# core.net
KiCad netlist of a schematic drawn in EAGLE
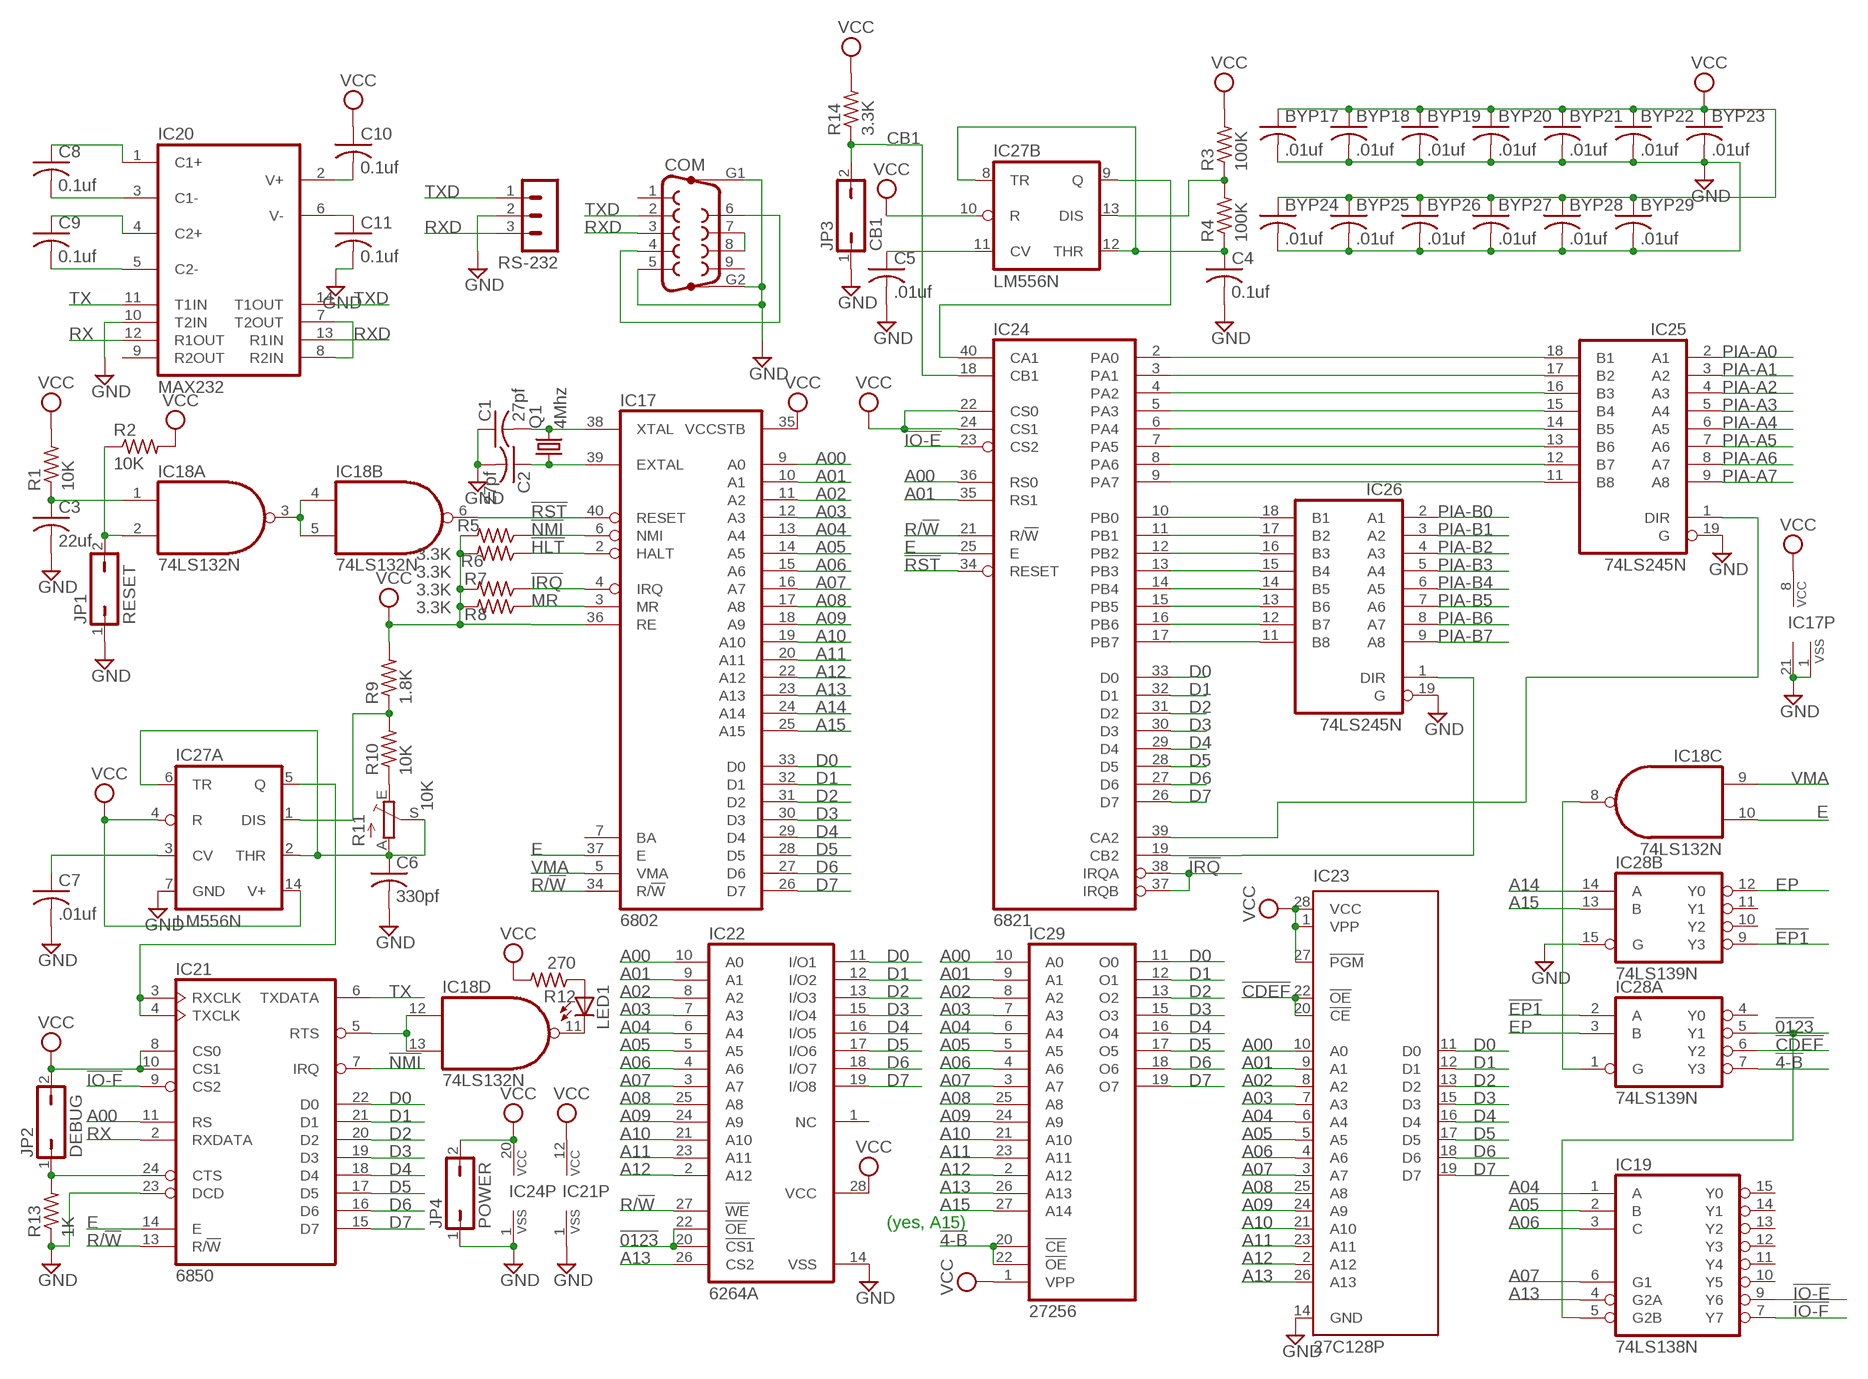
[diagram p0: schematic, sheet 1]
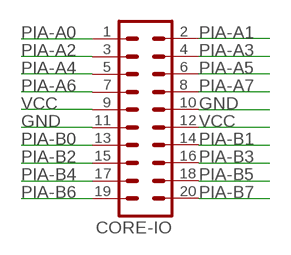
[diagram p1: schematic, sheet 2]

(export (version "E")
  (design (tool "Eeschema 10.0.6"))
  (components
    (comp (ref "CORE-IO")
      (value "MA10-2")
      (footprint "eagle-import:MA10-2")
      (libsource (lib "eagle-import") (part "MA10-2"))
    )
    (comp (ref "BYP17")
      (value ".01uf")
      (footprint "eagle-import:C050-025X075")
      (libsource (lib "eagle-import") (part "C-US050-025X075"))
    )
    (comp (ref "BYP18")
      (value ".01uf")
      (footprint "eagle-import:C050-025X075")
      (libsource (lib "eagle-import") (part "C-US050-025X075"))
    )
    (comp (ref "BYP19")
      (value ".01uf")
      (footprint "eagle-import:C050-025X075")
      (libsource (lib "eagle-import") (part "C-US050-025X075"))
    )
    (comp (ref "BYP20")
      (value ".01uf")
      (footprint "eagle-import:C050-025X075")
      (libsource (lib "eagle-import") (part "C-US050-025X075"))
    )
    (comp (ref "BYP21")
      (value ".01uf")
      (footprint "eagle-import:C050-025X075")
      (libsource (lib "eagle-import") (part "C-US050-025X075"))
    )
    (comp (ref "BYP22")
      (value ".01uf")
      (footprint "eagle-import:C050-025X075")
      (libsource (lib "eagle-import") (part "C-US050-025X075"))
    )
    (comp (ref "BYP23")
      (value ".01uf")
      (footprint "eagle-import:C050-025X075")
      (libsource (lib "eagle-import") (part "C-US050-025X075"))
    )
    (comp (ref "BYP24")
      (value ".01uf")
      (footprint "eagle-import:C050-025X075")
      (libsource (lib "eagle-import") (part "C-US050-025X075"))
    )
    (comp (ref "BYP25")
      (value ".01uf")
      (footprint "eagle-import:C050-025X075")
      (libsource (lib "eagle-import") (part "C-US050-025X075"))
    )
    (comp (ref "BYP26")
      (value ".01uf")
      (footprint "eagle-import:C050-025X075")
      (libsource (lib "eagle-import") (part "C-US050-025X075"))
    )
    (comp (ref "BYP27")
      (value ".01uf")
      (footprint "eagle-import:C050-025X075")
      (libsource (lib "eagle-import") (part "C-US050-025X075"))
    )
    (comp (ref "BYP28")
      (value ".01uf")
      (footprint "eagle-import:C050-025X075")
      (libsource (lib "eagle-import") (part "C-US050-025X075"))
    )
    (comp (ref "BYP29")
      (value ".01uf")
      (footprint "eagle-import:C050-025X075")
      (libsource (lib "eagle-import") (part "C-US050-025X075"))
    )
    (comp (ref "C1")
      (value "27pf")
      (footprint "eagle-import:C050-025X075")
      (libsource (lib "eagle-import") (part "C-US050-025X075"))
    )
    (comp (ref "C2")
      (value "27pf")
      (footprint "eagle-import:C050-025X075")
      (libsource (lib "eagle-import") (part "C-US050-025X075"))
    )
    (comp (ref "C3")
      (value "22uf")
      (footprint "eagle-import:C102-043X133")
      (libsource (lib "eagle-import") (part "C-US102-043X133"))
    )
    (comp (ref "C4")
      (value "0.1uf")
      (footprint "eagle-import:C050-025X075")
      (libsource (lib "eagle-import") (part "C-US050-025X075"))
    )
    (comp (ref "C5")
      (value ".01uf")
      (footprint "eagle-import:C050-025X075")
      (libsource (lib "eagle-import") (part "C-US050-025X075"))
    )
    (comp (ref "C6")
      (value "330pf")
      (footprint "eagle-import:C050-025X075")
      (libsource (lib "eagle-import") (part "C-US050-025X075"))
    )
    (comp (ref "C7")
      (value ".01uf")
      (footprint "eagle-import:C050-025X075")
      (libsource (lib "eagle-import") (part "C-US050-025X075"))
    )
    (comp (ref "C8")
      (value "0.1uf")
      (footprint "eagle-import:C050-025X075")
      (libsource (lib "eagle-import") (part "C-US050-025X075"))
    )
    (comp (ref "C9")
      (value "0.1uf")
      (footprint "eagle-import:C050-025X075")
      (libsource (lib "eagle-import") (part "C-US050-025X075"))
    )
    (comp (ref "C10")
      (value "0.1uf")
      (footprint "eagle-import:C050-025X075")
      (libsource (lib "eagle-import") (part "C-US050-025X075"))
    )
    (comp (ref "C11")
      (value "0.1uf")
      (footprint "eagle-import:C050-025X075")
      (libsource (lib "eagle-import") (part "C-US050-025X075"))
    )
    (comp (ref "COM")
      (value "F09HP")
      (footprint "eagle-import:F09HP")
      (libsource (lib "eagle-import") (part "F09HP"))
    )
    (comp (ref "IC17")
      (value "6802")
      (footprint "eagle-import:DIL40")
      (libsource (lib "eagle-import") (part "6802"))
    )
    (comp (ref "IC18")
      (value "74LS132N")
      (footprint "eagle-import:DIL14")
      (libsource (lib "eagle-import") (part "7400NLS"))
    )
    (comp (ref "IC19")
      (value "74LS138N")
      (footprint "eagle-import:DIL16")
      (libsource (lib "eagle-import") (part "74138NLS"))
    )
    (comp (ref "IC20")
      (value "MAX232")
      (footprint "eagle-import:DIL16")
      (fields (field (name "MF") "MAXIM") (field (name "MPN") "MAX232ACPE+"))
      (libsource (lib "eagle-import") (part "MAX232"))
    )
    (comp (ref "IC21")
      (value "6850")
      (footprint "eagle-import:DIL24")
      (fields (field (name "MF") "NTE ELECTRONICS") (field (name "MPN") "NTE6850"))
      (libsource (lib "eagle-import") (part "6850"))
    )
    (comp (ref "IC22")
      (value "6264A")
      (footprint "eagle-import:DIL28-6")
      (libsource (lib "eagle-import") (part "6264A"))
    )
    (comp (ref "IC23")
      (value "27C128P")
      (footprint "eagle-import:DIL28-6")
      (libsource (lib "eagle-import") (part "27128PC"))
    )
    (comp (ref "IC24")
      (value "6821")
      (footprint "eagle-import:DIL40")
      (fields (field (name "MF") "NTE ELECTRONICS") (field (name "MPN") "NTE6821"))
      (libsource (lib "eagle-import") (part "6821"))
    )
    (comp (ref "IC25")
      (value "74LS245N")
      (footprint "eagle-import:DIL20")
      (libsource (lib "eagle-import") (part "74245NLS"))
    )
    (comp (ref "IC26")
      (value "74LS245N")
      (footprint "eagle-import:DIL20")
      (libsource (lib "eagle-import") (part "74245NLS"))
    )
    (comp (ref "IC27")
      (value "LM556N")
      (footprint "eagle-import:DIL14")
      (libsource (lib "eagle-import") (part "556NLM"))
    )
    (comp (ref "IC28")
      (value "74LS139N")
      (footprint "eagle-import:DIL16")
      (libsource (lib "eagle-import") (part "74139NLS"))
    )
    (comp (ref "IC29")
      (value "27256")
      (footprint "eagle-import:DIL28")
      (libsource (lib "eagle-import") (part "27256"))
    )
    (comp (ref "JP1")
      (value "RESET")
      (footprint "eagle-import:JP1")
      (libsource (lib "eagle-import") (part "JP1Q"))
    )
    (comp (ref "JP2")
      (value "DEBUG")
      (footprint "eagle-import:JP1")
      (libsource (lib "eagle-import") (part "JP1Q"))
    )
    (comp (ref "JP3")
      (value "CB1")
      (footprint "eagle-import:JP1")
      (libsource (lib "eagle-import") (part "JP1Q"))
    )
    (comp (ref "JP4")
      (value "POWER")
      (footprint "eagle-import:JP1")
      (libsource (lib "eagle-import") (part "JP1Q"))
    )
    (comp (ref "LED1")
      (value "LED3MM")
      (footprint "eagle-import:LED3MM")
      (libsource (lib "eagle-import") (part "LED3MM"))
    )
    (comp (ref "Q1")
      (value "4Mhz")
      (footprint "eagle-import:HC18U-V")
      (libsource (lib "eagle-import") (part "CRYSTALHC18U-V"))
    )
    (comp (ref "R1")
      (value "10K")
      (footprint "eagle-import:0207_7")
      (libsource (lib "eagle-import") (part "R-US_0207/7"))
    )
    (comp (ref "R2")
      (value "10K")
      (footprint "eagle-import:0207_7")
      (libsource (lib "eagle-import") (part "R-US_0207/7"))
    )
    (comp (ref "R3")
      (value "100K")
      (footprint "eagle-import:0207_7")
      (libsource (lib "eagle-import") (part "R-US_0207/7"))
    )
    (comp (ref "R4")
      (value "100K")
      (footprint "eagle-import:0207_7")
      (libsource (lib "eagle-import") (part "R-US_0207/7"))
    )
    (comp (ref "R5")
      (value "3.3K")
      (footprint "eagle-import:0207_7")
      (libsource (lib "eagle-import") (part "R-US_0207/7"))
    )
    (comp (ref "R6")
      (value "3.3K")
      (footprint "eagle-import:0207_7")
      (libsource (lib "eagle-import") (part "R-US_0207/7"))
    )
    (comp (ref "R7")
      (value "3.3K")
      (footprint "eagle-import:0207_7")
      (libsource (lib "eagle-import") (part "R-US_0207/7"))
    )
    (comp (ref "R8")
      (value "3.3K")
      (footprint "eagle-import:0207_7")
      (libsource (lib "eagle-import") (part "R-US_0207/7"))
    )
    (comp (ref "R9")
      (value "1.8K")
      (footprint "eagle-import:0207_7")
      (libsource (lib "eagle-import") (part "R-US_0207/7"))
    )
    (comp (ref "R10")
      (value "10K")
      (footprint "eagle-import:0207_7")
      (libsource (lib "eagle-import") (part "R-US_0207/7"))
    )
    (comp (ref "R11")
      (value "10K")
      (footprint "eagle-import:SP19L")
      (libsource (lib "eagle-import") (part "TRIM_EU-B90P"))
    )
    (comp (ref "R12")
      (value "270")
      (footprint "eagle-import:0207_7")
      (libsource (lib "eagle-import") (part "R-US_0207/7"))
    )
    (comp (ref "R13")
      (value "1K")
      (footprint "eagle-import:0207_7")
      (libsource (lib "eagle-import") (part "R-US_0207/7"))
    )
    (comp (ref "R14")
      (value "3.3K")
      (footprint "eagle-import:0207_7")
      (libsource (lib "eagle-import") (part "R-US_0207/7"))
    )
    (comp (ref "RS-232")
      (value "MA03-1")
      (footprint "eagle-import:MA03-1")
      (libsource (lib "eagle-import") (part "MA03-1"))
    )
  )
  (nets
    (net (code "1") (name "A00") (class "Default")
      (node (ref "IC17") (pin "9") (pinfunction "A0_9") (pintype "output"))
      (node (ref "IC21") (pin "11") (pinfunction "RS_11") (pintype "input"))
      (node (ref "IC22") (pin "10") (pinfunction "A0_10") (pintype "input"))
      (node (ref "IC23") (pin "10") (pinfunction "A0_10") (pintype "input"))
      (node (ref "IC24") (pin "36") (pinfunction "RS0_36") (pintype "input"))
      (node (ref "IC29") (pin "10") (pinfunction "A0_10") (pintype "input"))
    )
    (net (code "2") (name "A01") (class "Default")
      (node (ref "IC17") (pin "10") (pinfunction "A1_10") (pintype "output"))
      (node (ref "IC22") (pin "9") (pinfunction "A1_9") (pintype "input"))
      (node (ref "IC23") (pin "9") (pinfunction "A1_9") (pintype "input"))
      (node (ref "IC24") (pin "35") (pinfunction "RS1_35") (pintype "input"))
      (node (ref "IC29") (pin "9") (pinfunction "A1_9") (pintype "input"))
    )
    (net (code "3") (name "A02") (class "Default")
      (node (ref "IC17") (pin "11") (pinfunction "A2_11") (pintype "output"))
      (node (ref "IC22") (pin "8") (pinfunction "A2_8") (pintype "input"))
      (node (ref "IC23") (pin "8") (pinfunction "A2_8") (pintype "input"))
      (node (ref "IC29") (pin "8") (pinfunction "A2_8") (pintype "input"))
    )
    (net (code "4") (name "A03") (class "Default")
      (node (ref "IC17") (pin "12") (pinfunction "A3_12") (pintype "output"))
      (node (ref "IC22") (pin "7") (pinfunction "A3_7") (pintype "input"))
      (node (ref "IC23") (pin "7") (pinfunction "A3_7") (pintype "input"))
      (node (ref "IC29") (pin "7") (pinfunction "A3_7") (pintype "input"))
    )
    (net (code "5") (name "A04") (class "Default")
      (node (ref "IC17") (pin "13") (pinfunction "A4_13") (pintype "output"))
      (node (ref "IC19") (pin "1") (pinfunction "A_1") (pintype "input"))
      (node (ref "IC22") (pin "6") (pinfunction "A4_6") (pintype "input"))
      (node (ref "IC23") (pin "6") (pinfunction "A4_6") (pintype "input"))
      (node (ref "IC29") (pin "6") (pinfunction "A4_6") (pintype "input"))
    )
    (net (code "6") (name "A05") (class "Default")
      (node (ref "IC17") (pin "14") (pinfunction "A5_14") (pintype "output"))
      (node (ref "IC19") (pin "2") (pinfunction "B_2") (pintype "input"))
      (node (ref "IC22") (pin "5") (pinfunction "A5_5") (pintype "input"))
      (node (ref "IC23") (pin "5") (pinfunction "A5_5") (pintype "input"))
      (node (ref "IC29") (pin "5") (pinfunction "A5_5") (pintype "input"))
    )
    (net (code "7") (name "A06") (class "Default")
      (node (ref "IC17") (pin "15") (pinfunction "A6_15") (pintype "output"))
      (node (ref "IC19") (pin "3") (pinfunction "C_3") (pintype "input"))
      (node (ref "IC22") (pin "4") (pinfunction "A6_4") (pintype "input"))
      (node (ref "IC23") (pin "4") (pinfunction "A6_4") (pintype "input"))
      (node (ref "IC29") (pin "4") (pinfunction "A6_4") (pintype "input"))
    )
    (net (code "8") (name "A07") (class "Default")
      (node (ref "IC17") (pin "16") (pinfunction "A7_16") (pintype "output"))
      (node (ref "IC19") (pin "6") (pinfunction "G1_6") (pintype "input"))
      (node (ref "IC22") (pin "3") (pinfunction "A7_3") (pintype "input"))
      (node (ref "IC23") (pin "3") (pinfunction "A7_3") (pintype "input"))
      (node (ref "IC29") (pin "3") (pinfunction "A7_3") (pintype "input"))
    )
    (net (code "9") (name "A08") (class "Default")
      (node (ref "IC17") (pin "17") (pinfunction "A8_17") (pintype "output"))
      (node (ref "IC22") (pin "25") (pinfunction "A8_25") (pintype "input"))
      (node (ref "IC23") (pin "25") (pinfunction "A8_25") (pintype "input"))
      (node (ref "IC29") (pin "25") (pinfunction "A8_25") (pintype "input"))
    )
    (net (code "10") (name "A09") (class "Default")
      (node (ref "IC17") (pin "18") (pinfunction "A9_18") (pintype "output"))
      (node (ref "IC22") (pin "24") (pinfunction "A9_24") (pintype "input"))
      (node (ref "IC23") (pin "24") (pinfunction "A9_24") (pintype "input"))
      (node (ref "IC29") (pin "24") (pinfunction "A9_24") (pintype "input"))
    )
    (net (code "11") (name "A10") (class "Default")
      (node (ref "IC17") (pin "19") (pinfunction "A10_19") (pintype "output"))
      (node (ref "IC22") (pin "21") (pinfunction "A10_21") (pintype "input"))
      (node (ref "IC23") (pin "21") (pinfunction "A10_21") (pintype "input"))
      (node (ref "IC29") (pin "21") (pinfunction "A10_21") (pintype "input"))
    )
    (net (code "12") (name "A11") (class "Default")
      (node (ref "IC17") (pin "20") (pinfunction "A11_20") (pintype "output"))
      (node (ref "IC22") (pin "23") (pinfunction "A11_23") (pintype "input"))
      (node (ref "IC23") (pin "23") (pinfunction "A11_23") (pintype "input"))
      (node (ref "IC29") (pin "23") (pinfunction "A11_23") (pintype "input"))
    )
    (net (code "13") (name "A12") (class "Default")
      (node (ref "IC17") (pin "22") (pinfunction "A12_22") (pintype "output"))
      (node (ref "IC22") (pin "2") (pinfunction "A12_2") (pintype "input"))
      (node (ref "IC23") (pin "2") (pinfunction "A12_2") (pintype "input"))
      (node (ref "IC29") (pin "2") (pinfunction "A12_2") (pintype "input"))
    )
    (net (code "14") (name "A13") (class "Default")
      (node (ref "IC17") (pin "23") (pinfunction "A13_23") (pintype "output"))
      (node (ref "IC19") (pin "4") (pinfunction "G2A_4") (pintype "input"))
      (node (ref "IC22") (pin "26") (pinfunction "CS2_26") (pintype "input"))
      (node (ref "IC23") (pin "26") (pinfunction "A13_26") (pintype "input"))
      (node (ref "IC29") (pin "26") (pinfunction "A13_26") (pintype "input"))
    )
    (net (code "15") (name "A14") (class "Default")
      (node (ref "IC17") (pin "24") (pinfunction "A14_24") (pintype "output"))
      (node (ref "IC28") (pin "14") (pinfunction "A_14") (pintype "input"))
    )
    (net (code "16") (name "A15") (class "Default")
      (node (ref "IC17") (pin "25") (pinfunction "A15_25") (pintype "output"))
      (node (ref "IC28") (pin "13") (pinfunction "B_13") (pintype "input"))
      (node (ref "IC29") (pin "27") (pinfunction "A14_27") (pintype "input"))
    )
    (net (code "17") (name "CB1") (class "Default")
      (node (ref "IC24") (pin "18") (pinfunction "CB1_18") (pintype "input"))
      (node (ref "JP3") (pin "2") (pinfunction "2_2") (pintype "passive"))
      (node (ref "R14") (pin "1") (pinfunction "1_1") (pintype "passive"))
    )
    (net (code "18") (name "D0") (class "Default")
      (node (ref "IC17") (pin "33") (pinfunction "D0_33") (pintype "bidirectional"))
      (node (ref "IC21") (pin "22") (pinfunction "D0_22") (pintype "bidirectional"))
      (node (ref "IC22") (pin "11") (pinfunction "I/O1_11") (pintype "bidirectional"))
      (node (ref "IC23") (pin "11") (pinfunction "D0_11") (pintype "tri_state"))
      (node (ref "IC24") (pin "33") (pinfunction "D0_33") (pintype "bidirectional"))
      (node (ref "IC29") (pin "11") (pinfunction "O0_11") (pintype "tri_state"))
    )
    (net (code "19") (name "D1") (class "Default")
      (node (ref "IC17") (pin "32") (pinfunction "D1_32") (pintype "bidirectional"))
      (node (ref "IC21") (pin "21") (pinfunction "D1_21") (pintype "bidirectional"))
      (node (ref "IC22") (pin "12") (pinfunction "I/O2_12") (pintype "bidirectional"))
      (node (ref "IC23") (pin "12") (pinfunction "D1_12") (pintype "tri_state"))
      (node (ref "IC24") (pin "32") (pinfunction "D1_32") (pintype "bidirectional"))
      (node (ref "IC29") (pin "12") (pinfunction "O1_12") (pintype "tri_state"))
    )
    (net (code "20") (name "D2") (class "Default")
      (node (ref "IC17") (pin "31") (pinfunction "D2_31") (pintype "bidirectional"))
      (node (ref "IC21") (pin "20") (pinfunction "D2_20") (pintype "bidirectional"))
      (node (ref "IC22") (pin "13") (pinfunction "I/O3_13") (pintype "bidirectional"))
      (node (ref "IC23") (pin "13") (pinfunction "D2_13") (pintype "tri_state"))
      (node (ref "IC24") (pin "31") (pinfunction "D2_31") (pintype "bidirectional"))
      (node (ref "IC29") (pin "13") (pinfunction "O2_13") (pintype "tri_state"))
    )
    (net (code "21") (name "D3") (class "Default")
      (node (ref "IC17") (pin "30") (pinfunction "D3_30") (pintype "bidirectional"))
      (node (ref "IC21") (pin "19") (pinfunction "D3_19") (pintype "bidirectional"))
      (node (ref "IC22") (pin "15") (pinfunction "I/O4_15") (pintype "bidirectional"))
      (node (ref "IC23") (pin "15") (pinfunction "D3_15") (pintype "tri_state"))
      (node (ref "IC24") (pin "30") (pinfunction "D3_30") (pintype "bidirectional"))
      (node (ref "IC29") (pin "15") (pinfunction "O3_15") (pintype "tri_state"))
    )
    (net (code "22") (name "D4") (class "Default")
      (node (ref "IC17") (pin "29") (pinfunction "D4_29") (pintype "bidirectional"))
      (node (ref "IC21") (pin "18") (pinfunction "D4_18") (pintype "bidirectional"))
      (node (ref "IC22") (pin "16") (pinfunction "I/O5_16") (pintype "bidirectional"))
      (node (ref "IC23") (pin "16") (pinfunction "D4_16") (pintype "tri_state"))
      (node (ref "IC24") (pin "29") (pinfunction "D4_29") (pintype "bidirectional"))
      (node (ref "IC29") (pin "16") (pinfunction "O4_16") (pintype "tri_state"))
    )
    (net (code "23") (name "D5") (class "Default")
      (node (ref "IC17") (pin "28") (pinfunction "D5_28") (pintype "bidirectional"))
      (node (ref "IC21") (pin "17") (pinfunction "D5_17") (pintype "bidirectional"))
      (node (ref "IC22") (pin "17") (pinfunction "I/O6_17") (pintype "bidirectional"))
      (node (ref "IC23") (pin "17") (pinfunction "D5_17") (pintype "tri_state"))
      (node (ref "IC24") (pin "28") (pinfunction "D5_28") (pintype "bidirectional"))
      (node (ref "IC29") (pin "17") (pinfunction "O5_17") (pintype "tri_state"))
    )
    (net (code "24") (name "D6") (class "Default")
      (node (ref "IC17") (pin "27") (pinfunction "D6_27") (pintype "bidirectional"))
      (node (ref "IC21") (pin "16") (pinfunction "D6_16") (pintype "bidirectional"))
      (node (ref "IC22") (pin "18") (pinfunction "I/O7_18") (pintype "bidirectional"))
      (node (ref "IC23") (pin "18") (pinfunction "D6_18") (pintype "tri_state"))
      (node (ref "IC24") (pin "27") (pinfunction "D6_27") (pintype "bidirectional"))
      (node (ref "IC29") (pin "18") (pinfunction "O6_18") (pintype "tri_state"))
    )
    (net (code "25") (name "D7") (class "Default")
      (node (ref "IC17") (pin "26") (pinfunction "D7_26") (pintype "bidirectional"))
      (node (ref "IC21") (pin "15") (pinfunction "D7_15") (pintype "bidirectional"))
      (node (ref "IC22") (pin "19") (pinfunction "I/O8_19") (pintype "bidirectional"))
      (node (ref "IC23") (pin "19") (pinfunction "D7_19") (pintype "tri_state"))
      (node (ref "IC24") (pin "26") (pinfunction "D7_26") (pintype "bidirectional"))
      (node (ref "IC29") (pin "19") (pinfunction "O7_19") (pintype "tri_state"))
    )
    (net (code "26") (name "E") (class "Default")
      (node (ref "IC17") (pin "37") (pinfunction "E_37") (pintype "output"))
      (node (ref "IC18") (pin "10") (pinfunction "I1_10") (pintype "input"))
      (node (ref "IC21") (pin "14") (pinfunction "E_14") (pintype "input"))
      (node (ref "IC24") (pin "25") (pinfunction "E_25") (pintype "input"))
    )
    (net (code "27") (name "EP") (class "Default")
      (node (ref "IC28") (pin "12") (pinfunction "Y0_12") (pintype "output"))
      (node (ref "IC28") (pin "3") (pinfunction "B_3") (pintype "input"))
    )
    (net (code "28") (name "GND") (class "Default")
      (node (ref "BYP17") (pin "2") (pinfunction "2_2") (pintype "passive"))
      (node (ref "BYP18") (pin "2") (pinfunction "2_2") (pintype "passive"))
      (node (ref "BYP19") (pin "2") (pinfunction "2_2") (pintype "passive"))
      (node (ref "BYP20") (pin "2") (pinfunction "2_2") (pintype "passive"))
      (node (ref "BYP21") (pin "2") (pinfunction "2_2") (pintype "passive"))
      (node (ref "BYP22") (pin "2") (pinfunction "2_2") (pintype "passive"))
      (node (ref "BYP23") (pin "2") (pinfunction "2_2") (pintype "passive"))
      (node (ref "BYP24") (pin "2") (pinfunction "2_2") (pintype "passive"))
      (node (ref "BYP25") (pin "2") (pinfunction "2_2") (pintype "passive"))
      (node (ref "BYP26") (pin "2") (pinfunction "2_2") (pintype "passive"))
      (node (ref "BYP27") (pin "2") (pinfunction "2_2") (pintype "passive"))
      (node (ref "BYP28") (pin "2") (pinfunction "2_2") (pintype "passive"))
      (node (ref "BYP29") (pin "2") (pinfunction "2_2") (pintype "passive"))
      (node (ref "C1") (pin "1") (pinfunction "1_1") (pintype "passive"))
      (node (ref "C11") (pin "2") (pinfunction "2_2") (pintype "passive"))
      (node (ref "C2") (pin "2") (pinfunction "2_2") (pintype "passive"))
      (node (ref "C3") (pin "2") (pinfunction "2_2") (pintype "passive"))
      (node (ref "C4") (pin "2") (pinfunction "2_2") (pintype "passive"))
      (node (ref "C5") (pin "2") (pinfunction "2_2") (pintype "passive"))
      (node (ref "C6") (pin "2") (pinfunction "2_2") (pintype "passive"))
      (node (ref "C7") (pin "2") (pinfunction "2_2") (pintype "passive"))
      (node (ref "COM") (pin "5") (pinfunction "5_5") (pintype "passive"))
      (node (ref "COM") (pin "G1") (pinfunction "G1_G1") (pintype "passive"))
      (node (ref "COM") (pin "G2") (pinfunction "G2_G2") (pintype "passive"))
      (node (ref "CORE-IO") (pin "10") (pinfunction "10_10") (pintype "passive"))
      (node (ref "CORE-IO") (pin "11") (pinfunction "11_11") (pintype "passive"))
      (node (ref "IC17") (pin "1") (pinfunction "VSS_1") (pintype "power_in"))
      (node (ref "IC17") (pin "21") (pinfunction "VSS_21") (pintype "power_in"))
      (node (ref "IC20") (pin "10") (pinfunction "T2IN_10") (pintype "input"))
      (node (ref "IC21") (pin "1") (pinfunction "VSS_1") (pintype "power_in"))
      (node (ref "IC21") (pin "23") (pinfunction "DCD_23") (pintype "input"))
      (node (ref "IC22") (pin "14") (pinfunction "VSS_14") (pintype "power_in"))
      (node (ref "IC23") (pin "14") (pinfunction "GND_14") (pintype "power_in"))
      (node (ref "IC24") (pin "1") (pinfunction "VSS_1") (pintype "power_in"))
      (node (ref "IC25") (pin "19") (pinfunction "G_19") (pintype "input"))
      (node (ref "IC26") (pin "19") (pinfunction "G_19") (pintype "input"))
      (node (ref "IC27") (pin "7") (pinfunction "GND_7") (pintype "power_in"))
      (node (ref "IC28") (pin "15") (pinfunction "G_15") (pintype "input"))
      (node (ref "JP1") (pin "1") (pinfunction "1_1") (pintype "passive"))
      (node (ref "JP3") (pin "1") (pinfunction "1_1") (pintype "passive"))
      (node (ref "JP4") (pin "1") (pinfunction "1_1") (pintype "passive"))
      (node (ref "R13") (pin "1") (pinfunction "1_1") (pintype "passive"))
      (node (ref "RS-232") (pin "2") (pinfunction "2_2") (pintype "passive"))
    )
    (net (code "29") (name "MR") (class "Default")
      (node (ref "IC17") (pin "3") (pinfunction "MR_3") (pintype "input"))
      (node (ref "R8") (pin "1") (pinfunction "1_1") (pintype "passive"))
    )
    (net (code "30") (name "Net-(COM-Pad4)") (class "Default")
      (node (ref "COM") (pin "4") (pinfunction "4_4") (pintype "passive"))
      (node (ref "COM") (pin "6") (pinfunction "6_6") (pintype "passive"))
    )
    (net (code "31") (name "Net-(COM-Pad7)") (class "Default")
      (node (ref "COM") (pin "7") (pinfunction "7_7") (pintype "passive"))
      (node (ref "COM") (pin "8") (pinfunction "8_8") (pintype "passive"))
    )
    (net (code "32") (name "Net-(IC17A-EXTAL)") (class "Default")
      (node (ref "C2") (pin "1") (pinfunction "1_1") (pintype "passive"))
      (node (ref "IC17") (pin "39") (pinfunction "EXTAL_39") (pintype "input"))
      (node (ref "Q1") (pin "1") (pinfunction "1_1") (pintype "passive"))
    )
    (net (code "33") (name "Net-(IC17A-XTAL)") (class "Default")
      (node (ref "C1") (pin "2") (pinfunction "2_2") (pintype "passive"))
      (node (ref "IC17") (pin "38") (pinfunction "XTAL_38") (pintype "input"))
      (node (ref "Q1") (pin "2") (pinfunction "2_2") (pintype "passive"))
    )
    (net (code "34") (name "Net-(IC18A-I0)") (class "Default")
      (node (ref "C3") (pin "1") (pinfunction "1_1") (pintype "passive"))
      (node (ref "IC18") (pin "1") (pinfunction "I0_1") (pintype "input"))
      (node (ref "R1") (pin "1") (pinfunction "1_1") (pintype "passive"))
    )
    (net (code "35") (name "Net-(IC18A-I1)") (class "Default")
      (node (ref "IC18") (pin "2") (pinfunction "I1_2") (pintype "input"))
      (node (ref "JP1") (pin "2") (pinfunction "2_2") (pintype "passive"))
      (node (ref "R2") (pin "1") (pinfunction "1_1") (pintype "passive"))
    )
    (net (code "36") (name "Net-(IC18A-O)") (class "Default")
      (node (ref "IC18") (pin "3") (pinfunction "O_3") (pintype "output"))
      (node (ref "IC18") (pin "4") (pinfunction "I0_4") (pintype "input"))
      (node (ref "IC18") (pin "5") (pinfunction "I1_5") (pintype "input"))
    )
    (net (code "37") (name "Net-(IC18C-O)") (class "Default")
      (node (ref "IC18") (pin "8") (pinfunction "O_8") (pintype "output"))
      (node (ref "IC28") (pin "1") (pinfunction "G_1") (pintype "input"))
    )
    (net (code "38") (name "Net-(IC18D-I0)") (class "Default")
      (node (ref "IC18") (pin "12") (pinfunction "I0_12") (pintype "input"))
      (node (ref "IC18") (pin "13") (pinfunction "I1_13") (pintype "input"))
      (node (ref "IC21") (pin "5") (pinfunction "RTS_5") (pintype "output"))
    )
    (net (code "39") (name "Net-(IC18D-O)") (class "Default")
      (node (ref "IC18") (pin "11") (pinfunction "O_11") (pintype "output"))
      (node (ref "LED1") (pin "K") (pinfunction "C_K") (pintype "passive"))
    )
    (net (code "40") (name "Net-(IC20A-C1+)") (class "Default")
      (node (ref "C8") (pin "1") (pinfunction "1_1") (pintype "passive"))
      (node (ref "IC20") (pin "1") (pinfunction "C1+_1") (pintype "bidirectional"))
    )
    (net (code "41") (name "Net-(IC20A-C1-)") (class "Default")
      (node (ref "C8") (pin "2") (pinfunction "2_2") (pintype "passive"))
      (node (ref "IC20") (pin "3") (pinfunction "C1-_3") (pintype "bidirectional"))
    )
    (net (code "42") (name "Net-(IC20A-C2+)") (class "Default")
      (node (ref "C9") (pin "1") (pinfunction "1_1") (pintype "passive"))
      (node (ref "IC20") (pin "4") (pinfunction "C2+_4") (pintype "bidirectional"))
    )
    (net (code "43") (name "Net-(IC20A-C2-)") (class "Default")
      (node (ref "C9") (pin "2") (pinfunction "2_2") (pintype "passive"))
      (node (ref "IC20") (pin "5") (pinfunction "C2-_5") (pintype "bidirectional"))
    )
    (net (code "44") (name "Net-(IC20A-R2IN)") (class "Default")
      (node (ref "IC20") (pin "7") (pinfunction "T2OUT_7") (pintype "output"))
      (node (ref "IC20") (pin "8") (pinfunction "R2IN_8") (pintype "input"))
    )
    (net (code "45") (name "Net-(IC20A-V+)") (class "Default")
      (node (ref "C10") (pin "2") (pinfunction "2_2") (pintype "passive"))
      (node (ref "IC20") (pin "2") (pinfunction "V+_2") (pintype "bidirectional"))
    )
    (net (code "46") (name "Net-(IC20A-V-)") (class "Default")
      (node (ref "C11") (pin "1") (pinfunction "1_1") (pintype "passive"))
      (node (ref "IC20") (pin "6") (pinfunction "V-_6") (pintype "bidirectional"))
    )
    (net (code "47") (name "Net-(IC21A-CTS)") (class "Default")
      (node (ref "IC21") (pin "24") (pinfunction "CTS_24") (pintype "input"))
      (node (ref "JP2") (pin "1") (pinfunction "1_1") (pintype "passive"))
      (node (ref "R13") (pin "2") (pinfunction "2_2") (pintype "passive"))
    )
    (net (code "48") (name "Net-(IC21A-RXCLK)") (class "Default")
      (node (ref "IC21") (pin "3") (pinfunction "RXCLK_3") (pintype "input"))
      (node (ref "IC21") (pin "4") (pinfunction "TXCLK_4") (pintype "input"))
      (node (ref "IC27") (pin "5") (pinfunction "Q_5") (pintype "output"))
    )
    (net (code "49") (name "Net-(IC24A-CA1)") (class "Default")
      (node (ref "IC24") (pin "40") (pinfunction "CA1_40") (pintype "input"))
      (node (ref "IC27") (pin "9") (pinfunction "Q_9") (pintype "output"))
    )
    (net (code "50") (name "Net-(IC24A-CA2)") (class "Default")
      (node (ref "IC24") (pin "39") (pinfunction "CA2_39") (pintype "bidirectional"))
      (node (ref "IC25") (pin "1") (pinfunction "DIR_1") (pintype "input"))
    )
    (net (code "51") (name "Net-(IC24A-CB2)") (class "Default")
      (node (ref "IC24") (pin "19") (pinfunction "CB2_19") (pintype "bidirectional"))
      (node (ref "IC26") (pin "1") (pinfunction "DIR_1") (pintype "input"))
    )
    (net (code "52") (name "Net-(IC24A-PA0)") (class "Default")
      (node (ref "IC24") (pin "2") (pinfunction "PA0_2") (pintype "bidirectional"))
      (node (ref "IC25") (pin "18") (pinfunction "B1_18") (pintype "bidirectional"))
    )
    (net (code "53") (name "Net-(IC24A-PA1)") (class "Default")
      (node (ref "IC24") (pin "3") (pinfunction "PA1_3") (pintype "bidirectional"))
      (node (ref "IC25") (pin "17") (pinfunction "B2_17") (pintype "bidirectional"))
    )
    (net (code "54") (name "Net-(IC24A-PA2)") (class "Default")
      (node (ref "IC24") (pin "4") (pinfunction "PA2_4") (pintype "bidirectional"))
      (node (ref "IC25") (pin "16") (pinfunction "B3_16") (pintype "bidirectional"))
    )
    (net (code "55") (name "Net-(IC24A-PA3)") (class "Default")
      (node (ref "IC24") (pin "5") (pinfunction "PA3_5") (pintype "bidirectional"))
      (node (ref "IC25") (pin "15") (pinfunction "B4_15") (pintype "bidirectional"))
    )
    (net (code "56") (name "Net-(IC24A-PA4)") (class "Default")
      (node (ref "IC24") (pin "6") (pinfunction "PA4_6") (pintype "bidirectional"))
      (node (ref "IC25") (pin "14") (pinfunction "B5_14") (pintype "bidirectional"))
    )
    (net (code "57") (name "Net-(IC24A-PA5)") (class "Default")
      (node (ref "IC24") (pin "7") (pinfunction "PA5_7") (pintype "bidirectional"))
      (node (ref "IC25") (pin "13") (pinfunction "B6_13") (pintype "bidirectional"))
    )
    (net (code "58") (name "Net-(IC24A-PA6)") (class "Default")
      (node (ref "IC24") (pin "8") (pinfunction "PA6_8") (pintype "bidirectional"))
      (node (ref "IC25") (pin "12") (pinfunction "B7_12") (pintype "bidirectional"))
    )
    (net (code "59") (name "Net-(IC24A-PA7)") (class "Default")
      (node (ref "IC24") (pin "9") (pinfunction "PA7_9") (pintype "bidirectional"))
      (node (ref "IC25") (pin "11") (pinfunction "B8_11") (pintype "bidirectional"))
    )
    (net (code "60") (name "Net-(IC24A-PB0)") (class "Default")
      (node (ref "IC24") (pin "10") (pinfunction "PB0_10") (pintype "bidirectional"))
      (node (ref "IC26") (pin "18") (pinfunction "B1_18") (pintype "bidirectional"))
    )
    (net (code "61") (name "Net-(IC24A-PB1)") (class "Default")
      (node (ref "IC24") (pin "11") (pinfunction "PB1_11") (pintype "bidirectional"))
      (node (ref "IC26") (pin "17") (pinfunction "B2_17") (pintype "bidirectional"))
    )
    (net (code "62") (name "Net-(IC24A-PB2)") (class "Default")
      (node (ref "IC24") (pin "12") (pinfunction "PB2_12") (pintype "bidirectional"))
      (node (ref "IC26") (pin "16") (pinfunction "B3_16") (pintype "bidirectional"))
    )
    (net (code "63") (name "Net-(IC24A-PB3)") (class "Default")
      (node (ref "IC24") (pin "13") (pinfunction "PB3_13") (pintype "bidirectional"))
      (node (ref "IC26") (pin "15") (pinfunction "B4_15") (pintype "bidirectional"))
    )
    (net (code "64") (name "Net-(IC24A-PB4)") (class "Default")
      (node (ref "IC24") (pin "14") (pinfunction "PB4_14") (pintype "bidirectional"))
      (node (ref "IC26") (pin "14") (pinfunction "B5_14") (pintype "bidirectional"))
    )
    (net (code "65") (name "Net-(IC24A-PB5)") (class "Default")
      (node (ref "IC24") (pin "15") (pinfunction "PB5_15") (pintype "bidirectional"))
      (node (ref "IC26") (pin "13") (pinfunction "B6_13") (pintype "bidirectional"))
    )
    (net (code "66") (name "Net-(IC24A-PB6)") (class "Default")
      (node (ref "IC24") (pin "16") (pinfunction "PB6_16") (pintype "bidirectional"))
      (node (ref "IC26") (pin "12") (pinfunction "B7_12") (pintype "bidirectional"))
    )
    (net (code "67") (name "Net-(IC24A-PB7)") (class "Default")
      (node (ref "IC24") (pin "17") (pinfunction "PB7_17") (pintype "bidirectional"))
      (node (ref "IC26") (pin "11") (pinfunction "B8_11") (pintype "bidirectional"))
    )
    (net (code "68") (name "Net-(IC27A-CV)") (class "Default")
      (node (ref "C7") (pin "1") (pinfunction "1_1") (pintype "passive"))
      (node (ref "IC27") (pin "3") (pinfunction "CV_3") (pintype "input"))
    )
    (net (code "69") (name "Net-(IC27A-DIS)") (class "Default")
      (node (ref "IC27") (pin "1") (pinfunction "DIS_1") (pintype "input"))
      (node (ref "R10") (pin "2") (pinfunction "2_2") (pintype "passive"))
      (node (ref "R9") (pin "1") (pinfunction "1_1") (pintype "passive"))
    )
    (net (code "70") (name "Net-(IC27A-THR)") (class "Default")
      (node (ref "C6") (pin "1") (pinfunction "1_1") (pintype "passive"))
      (node (ref "IC27") (pin "2") (pinfunction "THR_2") (pintype "input"))
      (node (ref "IC27") (pin "6") (pinfunction "TR_6") (pintype "input"))
      (node (ref "R11") (pin "A") (pinfunction "A_A") (pintype "passive"))
      (node (ref "R11") (pin "S") (pinfunction "S_S") (pintype "passive"))
    )
    (net (code "71") (name "Net-(IC27B-CV)") (class "Default")
      (node (ref "C5") (pin "1") (pinfunction "1_1") (pintype "passive"))
      (node (ref "IC27") (pin "11") (pinfunction "CV_11") (pintype "input"))
    )
    (net (code "72") (name "Net-(IC27B-DIS)") (class "Default")
      (node (ref "IC27") (pin "13") (pinfunction "DIS_13") (pintype "input"))
      (node (ref "R3") (pin "1") (pinfunction "1_1") (pintype "passive"))
      (node (ref "R4") (pin "2") (pinfunction "2_2") (pintype "passive"))
    )
    (net (code "73") (name "Net-(IC27B-THR)") (class "Default")
      (node (ref "C4") (pin "1") (pinfunction "1_1") (pintype "passive"))
      (node (ref "IC27") (pin "12") (pinfunction "THR_12") (pintype "input"))
      (node (ref "IC27") (pin "8") (pinfunction "TR_8") (pintype "input"))
      (node (ref "R4") (pin "1") (pinfunction "1_1") (pintype "passive"))
    )
    (net (code "74") (name "Net-(LED1-PadA)") (class "Default")
      (node (ref "LED1") (pin "A") (pinfunction "A_A") (pintype "passive"))
      (node (ref "R12") (pin "1") (pinfunction "1_1") (pintype "passive"))
    )
    (net (code "75") (name "Net-(R10-Pad1)") (class "Default")
      (node (ref "R10") (pin "1") (pinfunction "1_1") (pintype "passive"))
      (node (ref "R11") (pin "E") (pinfunction "E_E") (pintype "passive"))
    )
    (net (code "76") (name "PIA-A0") (class "Default")
      (node (ref "CORE-IO") (pin "1") (pinfunction "1_1") (pintype "passive"))
      (node (ref "IC25") (pin "2") (pinfunction "A1_2") (pintype "bidirectional"))
    )
    (net (code "77") (name "PIA-A1") (class "Default")
      (node (ref "CORE-IO") (pin "2") (pinfunction "2_2") (pintype "passive"))
      (node (ref "IC25") (pin "3") (pinfunction "A2_3") (pintype "bidirectional"))
    )
    (net (code "78") (name "PIA-A2") (class "Default")
      (node (ref "CORE-IO") (pin "3") (pinfunction "3_3") (pintype "passive"))
      (node (ref "IC25") (pin "4") (pinfunction "A3_4") (pintype "bidirectional"))
    )
    (net (code "79") (name "PIA-A3") (class "Default")
      (node (ref "CORE-IO") (pin "4") (pinfunction "4_4") (pintype "passive"))
      (node (ref "IC25") (pin "5") (pinfunction "A4_5") (pintype "bidirectional"))
    )
    (net (code "80") (name "PIA-A4") (class "Default")
      (node (ref "CORE-IO") (pin "5") (pinfunction "5_5") (pintype "passive"))
      (node (ref "IC25") (pin "6") (pinfunction "A5_6") (pintype "bidirectional"))
    )
    (net (code "81") (name "PIA-A5") (class "Default")
      (node (ref "CORE-IO") (pin "6") (pinfunction "6_6") (pintype "passive"))
      (node (ref "IC25") (pin "7") (pinfunction "A6_7") (pintype "bidirectional"))
    )
    (net (code "82") (name "PIA-A6") (class "Default")
      (node (ref "CORE-IO") (pin "7") (pinfunction "7_7") (pintype "passive"))
      (node (ref "IC25") (pin "8") (pinfunction "A7_8") (pintype "bidirectional"))
    )
    (net (code "83") (name "PIA-A7") (class "Default")
      (node (ref "CORE-IO") (pin "8") (pinfunction "8_8") (pintype "passive"))
      (node (ref "IC25") (pin "9") (pinfunction "A8_9") (pintype "bidirectional"))
    )
    (net (code "84") (name "PIA-B0") (class "Default")
      (node (ref "CORE-IO") (pin "13") (pinfunction "13_13") (pintype "passive"))
      (node (ref "IC26") (pin "2") (pinfunction "A1_2") (pintype "bidirectional"))
    )
    (net (code "85") (name "PIA-B1") (class "Default")
      (node (ref "CORE-IO") (pin "14") (pinfunction "14_14") (pintype "passive"))
      (node (ref "IC26") (pin "3") (pinfunction "A2_3") (pintype "bidirectional"))
    )
    (net (code "86") (name "PIA-B2") (class "Default")
      (node (ref "CORE-IO") (pin "15") (pinfunction "15_15") (pintype "passive"))
      (node (ref "IC26") (pin "4") (pinfunction "A3_4") (pintype "bidirectional"))
    )
    (net (code "87") (name "PIA-B3") (class "Default")
      (node (ref "CORE-IO") (pin "16") (pinfunction "16_16") (pintype "passive"))
      (node (ref "IC26") (pin "5") (pinfunction "A4_5") (pintype "bidirectional"))
    )
    (net (code "88") (name "PIA-B4") (class "Default")
      (node (ref "CORE-IO") (pin "17") (pinfunction "17_17") (pintype "passive"))
      (node (ref "IC26") (pin "6") (pinfunction "A5_6") (pintype "bidirectional"))
    )
    (net (code "89") (name "PIA-B5") (class "Default")
      (node (ref "CORE-IO") (pin "18") (pinfunction "18_18") (pintype "passive"))
      (node (ref "IC26") (pin "7") (pinfunction "A6_7") (pintype "bidirectional"))
    )
    (net (code "90") (name "PIA-B6") (class "Default")
      (node (ref "CORE-IO") (pin "19") (pinfunction "19_19") (pintype "passive"))
      (node (ref "IC26") (pin "8") (pinfunction "A7_8") (pintype "bidirectional"))
    )
    (net (code "91") (name "PIA-B7") (class "Default")
      (node (ref "CORE-IO") (pin "20") (pinfunction "20_20") (pintype "passive"))
      (node (ref "IC26") (pin "9") (pinfunction "A8_9") (pintype "bidirectional"))
    )
    (net (code "92") (name "RX") (class "Default")
      (node (ref "IC20") (pin "12") (pinfunction "R1OUT_12") (pintype "output"))
      (node (ref "IC21") (pin "2") (pinfunction "RXDATA_2") (pintype "input"))
    )
    (net (code "93") (name "RXD") (class "Default")
      (node (ref "COM") (pin "3") (pinfunction "3_3") (pintype "passive"))
      (node (ref "IC20") (pin "13") (pinfunction "R1IN_13") (pintype "input"))
      (node (ref "RS-232") (pin "3") (pinfunction "3_3") (pintype "passive"))
    )
    (net (code "94") (name "R{slash}~{W}") (class "Default")
      (node (ref "IC17") (pin "34") (pinfunction "R/~{W}_34") (pintype "output"))
      (node (ref "IC21") (pin "13") (pinfunction "R/~{W}_13") (pintype "input"))
      (node (ref "IC22") (pin "27") (pinfunction "~{WE}_27") (pintype "input"))
      (node (ref "IC24") (pin "21") (pinfunction "R/~{W}_21") (pintype "input"))
    )
    (net (code "95") (name "TX") (class "Default")
      (node (ref "IC20") (pin "11") (pinfunction "T1IN_11") (pintype "input"))
      (node (ref "IC21") (pin "6") (pinfunction "TXDATA_6") (pintype "output"))
    )
    (net (code "96") (name "TXD") (class "Default")
      (node (ref "COM") (pin "2") (pinfunction "2_2") (pintype "passive"))
      (node (ref "IC20") (pin "14") (pinfunction "T1OUT_14") (pintype "output"))
      (node (ref "RS-232") (pin "1") (pinfunction "1_1") (pintype "passive"))
    )
    (net (code "97") (name "VCC") (class "Default")
      (node (ref "BYP17") (pin "1") (pinfunction "1_1") (pintype "passive"))
      (node (ref "BYP18") (pin "1") (pinfunction "1_1") (pintype "passive"))
      (node (ref "BYP19") (pin "1") (pinfunction "1_1") (pintype "passive"))
      (node (ref "BYP20") (pin "1") (pinfunction "1_1") (pintype "passive"))
      (node (ref "BYP21") (pin "1") (pinfunction "1_1") (pintype "passive"))
      (node (ref "BYP22") (pin "1") (pinfunction "1_1") (pintype "passive"))
      (node (ref "BYP23") (pin "1") (pinfunction "1_1") (pintype "passive"))
      (node (ref "BYP24") (pin "1") (pinfunction "1_1") (pintype "passive"))
      (node (ref "BYP25") (pin "1") (pinfunction "1_1") (pintype "passive"))
      (node (ref "BYP26") (pin "1") (pinfunction "1_1") (pintype "passive"))
      (node (ref "BYP27") (pin "1") (pinfunction "1_1") (pintype "passive"))
      (node (ref "BYP28") (pin "1") (pinfunction "1_1") (pintype "passive"))
      (node (ref "BYP29") (pin "1") (pinfunction "1_1") (pintype "passive"))
      (node (ref "C10") (pin "1") (pinfunction "1_1") (pintype "passive"))
      (node (ref "CORE-IO") (pin "12") (pinfunction "12_12") (pintype "passive"))
      (node (ref "CORE-IO") (pin "9") (pinfunction "9_9") (pintype "passive"))
      (node (ref "IC17") (pin "35") (pinfunction "VCCSTB_35") (pintype "input"))
      (node (ref "IC17") (pin "36") (pinfunction "RE_36") (pintype "input"))
      (node (ref "IC17") (pin "8") (pinfunction "VCC_8") (pintype "power_in"))
      (node (ref "IC21") (pin "10") (pinfunction "CS1_10") (pintype "input"))
      (node (ref "IC21") (pin "12") (pinfunction "VCC_12") (pintype "power_in"))
      (node (ref "IC21") (pin "8") (pinfunction "CS0_8") (pintype "input"))
      (node (ref "IC22") (pin "28") (pinfunction "VCC_28") (pintype "power_in"))
      (node (ref "IC23") (pin "1") (pinfunction "VPP_1") (pintype "input"))
      (node (ref "IC23") (pin "27") (pinfunction "~{PGM}_27") (pintype "passive"))
      (node (ref "IC23") (pin "28") (pinfunction "VCC_28") (pintype "power_in"))
      (node (ref "IC24") (pin "20") (pinfunction "VCC_20") (pintype "power_in"))
      (node (ref "IC24") (pin "22") (pinfunction "CS0_22") (pintype "input"))
      (node (ref "IC24") (pin "24") (pinfunction "CS1_24") (pintype "input"))
      (node (ref "IC27") (pin "10") (pinfunction "R_10") (pintype "input"))
      (node (ref "IC27") (pin "14") (pinfunction "V+_14") (pintype "power_in"))
      (node (ref "IC27") (pin "4") (pinfunction "R_4") (pintype "input"))
      (node (ref "IC29") (pin "1") (pinfunction "VPP_1") (pintype "input"))
      (node (ref "JP2") (pin "2") (pinfunction "2_2") (pintype "passive"))
      (node (ref "JP4") (pin "2") (pinfunction "2_2") (pintype "passive"))
      (node (ref "R1") (pin "2") (pinfunction "2_2") (pintype "passive"))
      (node (ref "R12") (pin "2") (pinfunction "2_2") (pintype "passive"))
      (node (ref "R14") (pin "2") (pinfunction "2_2") (pintype "passive"))
      (node (ref "R2") (pin "2") (pinfunction "2_2") (pintype "passive"))
      (node (ref "R3") (pin "2") (pinfunction "2_2") (pintype "passive"))
      (node (ref "R5") (pin "2") (pinfunction "2_2") (pintype "passive"))
      (node (ref "R6") (pin "2") (pinfunction "2_2") (pintype "passive"))
      (node (ref "R7") (pin "2") (pinfunction "2_2") (pintype "passive"))
      (node (ref "R8") (pin "2") (pinfunction "2_2") (pintype "passive"))
      (node (ref "R9") (pin "2") (pinfunction "2_2") (pintype "passive"))
    )
    (net (code "98") (name "VMA") (class "Default")
      (node (ref "IC17") (pin "5") (pinfunction "VMA_5") (pintype "output"))
      (node (ref "IC18") (pin "9") (pinfunction "I0_9") (pintype "input"))
    )
    (net (code "99") (name "unconnected-(COM-Pad1)") (class "Default")
      (node (ref "COM") (pin "1") (pinfunction "1_1") (pintype "passive"))
    )
    (net (code "100") (name "unconnected-(COM-Pad9)") (class "Default")
      (node (ref "COM") (pin "9") (pinfunction "9_9") (pintype "passive"))
    )
    (net (code "101") (name "unconnected-(IC17A-BA-Pad7)") (class "Default")
      (node (ref "IC17") (pin "7") (pinfunction "BA_7") (pintype "output"))
    )
    (net (code "102") (name "unconnected-(IC19A-Y0-Pad15)") (class "Default")
      (node (ref "IC19") (pin "15") (pinfunction "Y0_15") (pintype "output"))
    )
    (net (code "103") (name "unconnected-(IC19A-Y1-Pad14)") (class "Default")
      (node (ref "IC19") (pin "14") (pinfunction "Y1_14") (pintype "output"))
    )
    (net (code "104") (name "unconnected-(IC19A-Y2-Pad13)") (class "Default")
      (node (ref "IC19") (pin "13") (pinfunction "Y2_13") (pintype "output"))
    )
    (net (code "105") (name "unconnected-(IC19A-Y3-Pad12)") (class "Default")
      (node (ref "IC19") (pin "12") (pinfunction "Y3_12") (pintype "output"))
    )
    (net (code "106") (name "unconnected-(IC19A-Y4-Pad11)") (class "Default")
      (node (ref "IC19") (pin "11") (pinfunction "Y4_11") (pintype "output"))
    )
    (net (code "107") (name "unconnected-(IC19A-Y5-Pad10)") (class "Default")
      (node (ref "IC19") (pin "10") (pinfunction "Y5_10") (pintype "output"))
    )
    (net (code "108") (name "unconnected-(IC20A-R2OUT-Pad9)") (class "Default")
      (node (ref "IC20") (pin "9") (pinfunction "R2OUT_9") (pintype "output"))
    )
    (net (code "109") (name "unconnected-(IC22-NC-Pad1)") (class "Default")
      (node (ref "IC22") (pin "1") (pinfunction "NC_1") (pintype "no_connect"))
    )
    (net (code "110") (name "unconnected-(IC28A-Y0-Pad4)") (class "Default")
      (node (ref "IC28") (pin "4") (pinfunction "Y0_4") (pintype "output"))
    )
    (net (code "111") (name "unconnected-(IC28B-Y1-Pad11)") (class "Default")
      (node (ref "IC28") (pin "11") (pinfunction "Y1_11") (pintype "output"))
    )
    (net (code "112") (name "unconnected-(IC28B-Y2-Pad10)") (class "Default")
      (node (ref "IC28") (pin "10") (pinfunction "Y2_10") (pintype "output"))
    )
    (net (code "113") (name "~{4-B}") (class "Default")
      (node (ref "IC28") (pin "7") (pinfunction "Y3_7") (pintype "output"))
      (node (ref "IC29") (pin "20") (pinfunction "~{CE}_20") (pintype "input"))
      (node (ref "IC29") (pin "22") (pinfunction "~{OE}_22") (pintype "input"))
    )
    (net (code "114") (name "~{0123}") (class "Default")
      (node (ref "IC19") (pin "5") (pinfunction "G2B_5") (pintype "input"))
      (node (ref "IC22") (pin "20") (pinfunction "~{CS1}_20") (pintype "input"))
      (node (ref "IC22") (pin "22") (pinfunction "~{OE}_22") (pintype "input"))
      (node (ref "IC28") (pin "5") (pinfunction "Y1_5") (pintype "output"))
    )
    (net (code "115") (name "~{CDEF}") (class "Default")
      (node (ref "IC23") (pin "20") (pinfunction "~{CE}_20") (pintype "input"))
      (node (ref "IC23") (pin "22") (pinfunction "~{OE}_22") (pintype "input"))
      (node (ref "IC28") (pin "6") (pinfunction "Y2_6") (pintype "output"))
    )
    (net (code "116") (name "~{EP1}") (class "Default")
      (node (ref "IC28") (pin "2") (pinfunction "A_2") (pintype "input"))
      (node (ref "IC28") (pin "9") (pinfunction "Y3_9") (pintype "output"))
    )
    (net (code "117") (name "~{HLT}") (class "Default")
      (node (ref "IC17") (pin "2") (pinfunction "HALT_2") (pintype "input"))
      (node (ref "R5") (pin "1") (pinfunction "1_1") (pintype "passive"))
    )
    (net (code "118") (name "~{IO-E}") (class "Default")
      (node (ref "IC19") (pin "9") (pinfunction "Y6_9") (pintype "output"))
      (node (ref "IC24") (pin "23") (pinfunction "CS2_23") (pintype "input"))
    )
    (net (code "119") (name "~{IO-F}") (class "Default")
      (node (ref "IC19") (pin "7") (pinfunction "Y7_7") (pintype "output"))
      (node (ref "IC21") (pin "9") (pinfunction "CS2_9") (pintype "input"))
    )
    (net (code "120") (name "~{IRQ}") (class "Default")
      (node (ref "IC17") (pin "4") (pinfunction "IRQ_4") (pintype "input"))
      (node (ref "IC24") (pin "37") (pinfunction "IRQB_37") (pintype "open_collector"))
      (node (ref "IC24") (pin "38") (pinfunction "IRQA_38") (pintype "open_collector"))
      (node (ref "R7") (pin "1") (pinfunction "1_1") (pintype "passive"))
    )
    (net (code "121") (name "~{NMI}") (class "Default")
      (node (ref "IC17") (pin "6") (pinfunction "NMI_6") (pintype "input"))
      (node (ref "IC21") (pin "7") (pinfunction "IRQ_7") (pintype "output"))
      (node (ref "R6") (pin "1") (pinfunction "1_1") (pintype "passive"))
    )
    (net (code "122") (name "~{RST}") (class "Default")
      (node (ref "IC17") (pin "40") (pinfunction "RESET_40") (pintype "input"))
      (node (ref "IC18") (pin "6") (pinfunction "O_6") (pintype "output"))
      (node (ref "IC24") (pin "34") (pinfunction "RESET_34") (pintype "input"))
    )
  )
)
